# fonte-de-tensao.net
KiCad netlist of a schematic drawn in EAGLE
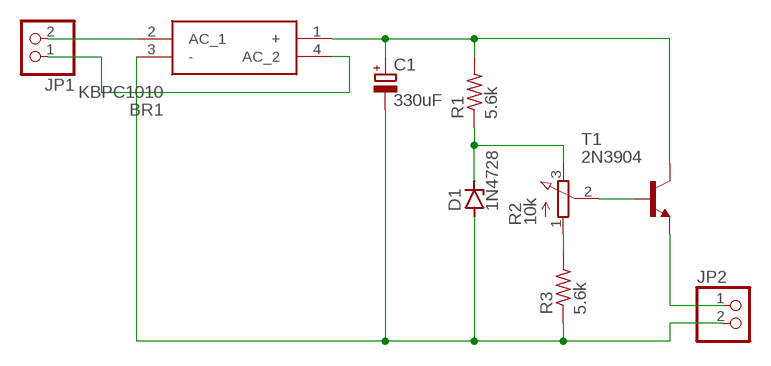
[diagram p0: schematic, sheet 1]

(export (version "E")
  (design (tool "Eeschema 10.0.6"))
  (components
    (comp (ref "BR1")
      (value "KBPC1010")
      (footprint "eagle-import:KBPC1010")
      (libsource (lib "eagle-import") (part "KBPC1010"))
    )
    (comp (ref "C1")
      (value "330uF")
      (footprint "eagle-import:E3,5-10")
      (libsource (lib "eagle-import") (part "CPOL-EUE3.5-10"))
    )
    (comp (ref "D1")
      (value "1N4728")
      (footprint "eagle-import:DO41Z10")
      (libsource (lib "eagle-import") (part "1N4728"))
    )
    (comp (ref "JP1")
      (value "PINHD-1X2")
      (footprint "eagle-import:1X02")
      (libsource (lib "eagle-import") (part "PINHD-1X2"))
    )
    (comp (ref "JP2")
      (value "PINHD-1X2")
      (footprint "eagle-import:1X02")
      (libsource (lib "eagle-import") (part "PINHD-1X2"))
    )
    (comp (ref "R1")
      (value "5.6k")
      (footprint "eagle-import:0309_12")
      (libsource (lib "eagle-import") (part "R-US_0309/12"))
    )
    (comp (ref "R2")
      (value "10k")
      (footprint "eagle-import:3RP_1610N")
      (libsource (lib "eagle-import") (part "3RP/1610N"))
    )
    (comp (ref "R3")
      (value "5.6k")
      (footprint "eagle-import:0309_12")
      (libsource (lib "eagle-import") (part "R-US_0309/12"))
    )
    (comp (ref "T1")
      (value "2N3904")
      (footprint "eagle-import:TO92")
      (libsource (lib "eagle-import") (part "2N3904"))
    )
  )
  (nets
    (net (code "1") (name "Net-(BR1-+)") (class "Default")
      (node (ref "BR1") (pin "1") (pinfunction "+_1") (pintype "bidirectional"))
      (node (ref "C1") (pin "+") (pinfunction "+_+") (pintype "passive"))
      (node (ref "R1") (pin "2") (pinfunction "2_2") (pintype "passive"))
      (node (ref "T1") (pin "1") (pinfunction "C_1") (pintype "passive"))
    )
    (net (code "2") (name "Net-(BR1--)") (class "Default")
      (node (ref "BR1") (pin "3") (pinfunction "-_3") (pintype "bidirectional"))
      (node (ref "C1") (pin "-") (pinfunction "-_-") (pintype "passive"))
      (node (ref "D1") (pin "A") (pinfunction "A_A") (pintype "passive"))
      (node (ref "JP2") (pin "2") (pinfunction "2_2") (pintype "passive"))
      (node (ref "R3") (pin "1") (pinfunction "1_1") (pintype "passive"))
    )
    (net (code "3") (name "Net-(BR1-AC_1)") (class "Default")
      (node (ref "BR1") (pin "2") (pinfunction "AC_1_2") (pintype "bidirectional"))
      (node (ref "JP1") (pin "2") (pinfunction "2_2") (pintype "passive"))
    )
    (net (code "4") (name "Net-(BR1-AC_2)") (class "Default")
      (node (ref "BR1") (pin "4") (pinfunction "AC_2_4") (pintype "bidirectional"))
      (node (ref "JP1") (pin "1") (pinfunction "1_1") (pintype "passive"))
    )
    (net (code "5") (name "Net-(R2-A)") (class "Default")
      (node (ref "R2") (pin "1") (pinfunction "A_1") (pintype "passive"))
      (node (ref "R3") (pin "2") (pinfunction "2_2") (pintype "passive"))
    )
    (net (code "6") (name "Net-(R2-E)") (class "Default")
      (node (ref "D1") (pin "C") (pinfunction "C_C") (pintype "passive"))
      (node (ref "R1") (pin "1") (pinfunction "1_1") (pintype "passive"))
      (node (ref "R2") (pin "3") (pinfunction "E_3") (pintype "passive"))
    )
    (net (code "7") (name "Net-(R2-S)") (class "Default")
      (node (ref "R2") (pin "2") (pinfunction "S_2") (pintype "passive"))
      (node (ref "T1") (pin "2") (pinfunction "B_2") (pintype "passive"))
    )
    (net (code "8") (name "Net-(T1-E)") (class "Default")
      (node (ref "JP2") (pin "1") (pinfunction "1_1") (pintype "passive"))
      (node (ref "T1") (pin "3") (pinfunction "E_3") (pintype "passive"))
    )
  )
)
